# Crystal.net
KiCad netlist of a schematic drawn in Altium Designer
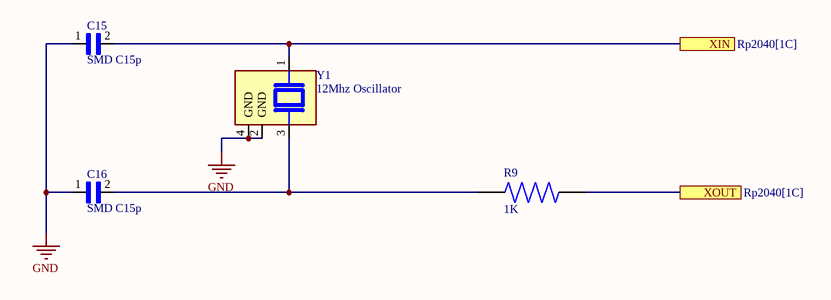
[diagram p0: Crystal.SchDoc]

(export (version "E")
  (design (tool "Eeschema 10.0.6"))
  (components
    (comp (ref "C15")
      (value "SMD C15p")
      (footprint "SMD Capacetor-Footprint-1")
      (description "Generic SMD Capacetor")
      (libsource (lib "Tobias") (part "15p"))
    )
    (comp (ref "C16")
      (value "SMD C15p")
      (footprint "SMD Capacetor-Footprint-1")
      (description "Generic SMD Capacetor")
      (libsource (lib "Tobias") (part "15p"))
    )
    (comp (ref "R9")
      (value "1K")
      (footprint "SMD Resistor-Footprint-1")
      (description "Generic SMD Resistor")
      (libsource (lib "Tobias") (part "SMD Resistor-Symbol-1"))
    )
    (comp (ref "Y1")
      (value "12Mhz Oscillator")
      (footprint "12Mhz Oscillator-Footprint-1")
      (description "12 Mhz Oscillator SMD")
      (libsource (lib "Tobias") (part "12Mhz Oscillator-Symbol-1"))
    )
  )
  (nets
    (net (code "1") (name "/XIN") (class "Default")
      (node (ref "C15") (pin "2") (pinfunction "2_2") (pintype "passive"))
      (node (ref "Y1") (pin "1") (pinfunction "1_1") (pintype "passive"))
    )
    (net (code "2") (name "/XOUT") (class "Default")
      (node (ref "R9") (pin "2") (pinfunction "2_2") (pintype "passive"))
    )
    (net (code "3") (name "GND") (class "Default")
      (node (ref "C15") (pin "1") (pinfunction "1_1") (pintype "passive"))
      (node (ref "C16") (pin "1") (pinfunction "1_1") (pintype "passive"))
      (node (ref "Y1") (pin "2") (pinfunction "GND_2") (pintype "power_in"))
      (node (ref "Y1") (pin "4") (pinfunction "GND_4") (pintype "power_in"))
    )
    (net (code "4") (name "Net-(Y1-2)") (class "Default")
      (node (ref "C16") (pin "2") (pinfunction "2_2") (pintype "passive"))
      (node (ref "R9") (pin "1") (pinfunction "1_1") (pintype "passive"))
      (node (ref "Y1") (pin "3") (pinfunction "2_3") (pintype "passive"))
    )
  )
)
